# 52.net
KiCad netlist of a schematic drawn in Altium Designer
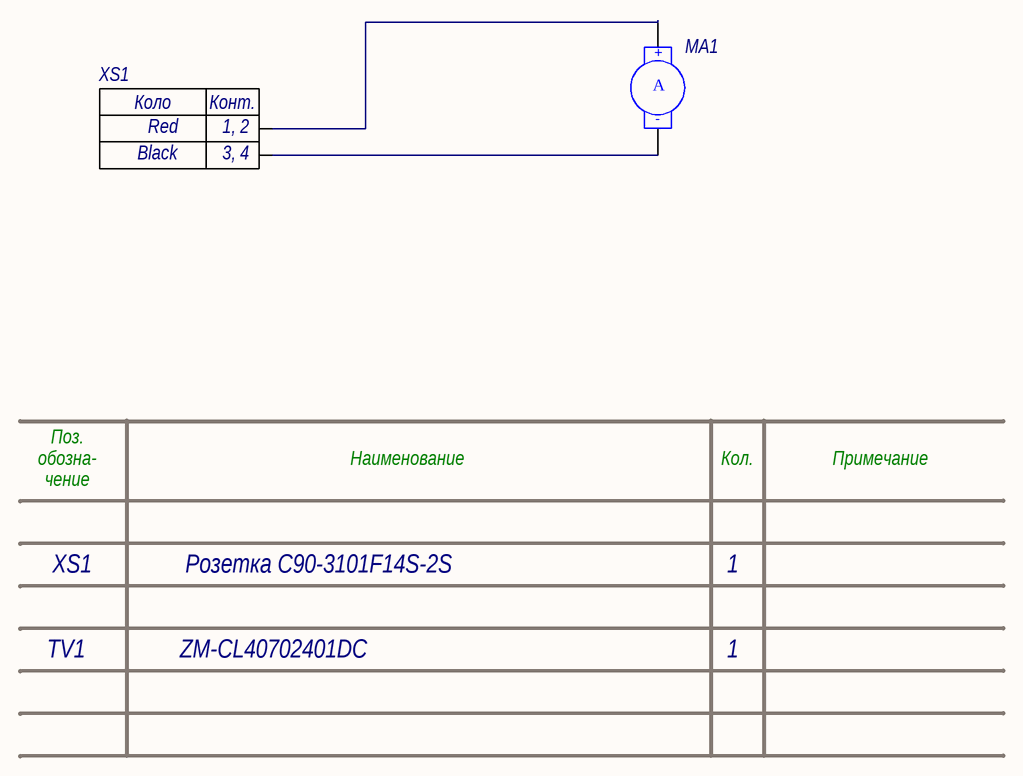
[diagram p0: АЧАД.52хххх.ххх.SchDoc]

(export (version "E")
  (design (tool "Eeschema 10.0.6"))
  (components
    (comp (ref "MA1")
      (value "Motor Servo")
      (footprint "RAD-0.4")
      (description "Servo Motor")
      (fields (field (name "PUBLISHER") "Altium Limited"))
      (libsource (lib "Miscellaneous Devices") (part "Motor Servo"))
    )
    (comp (ref "XS1") (value "M20-9770242") (libsource (lib "АСК_1") (part "M20-9770242")))
  )
  (nets
    (net (code "1") (name "Net-(MA1-+)") (class "Default")
      (node (ref "MA1") (pin "1") (pinfunction "+_1") (pintype "passive"))
      (node (ref "XS1") (pin "1") (pinfunction "1_,2_1") (pintype "passive"))
    )
    (net (code "2") (name "Net-(MA1--)") (class "Default")
      (node (ref "MA1") (pin "2") (pinfunction "-_2") (pintype "passive"))
      (node (ref "XS1") (pin "2") (pinfunction "3_,4_2") (pintype "passive"))
    )
  )
)
